# CircuitArd.net
KiCad netlist of a schematic drawn in EAGLE
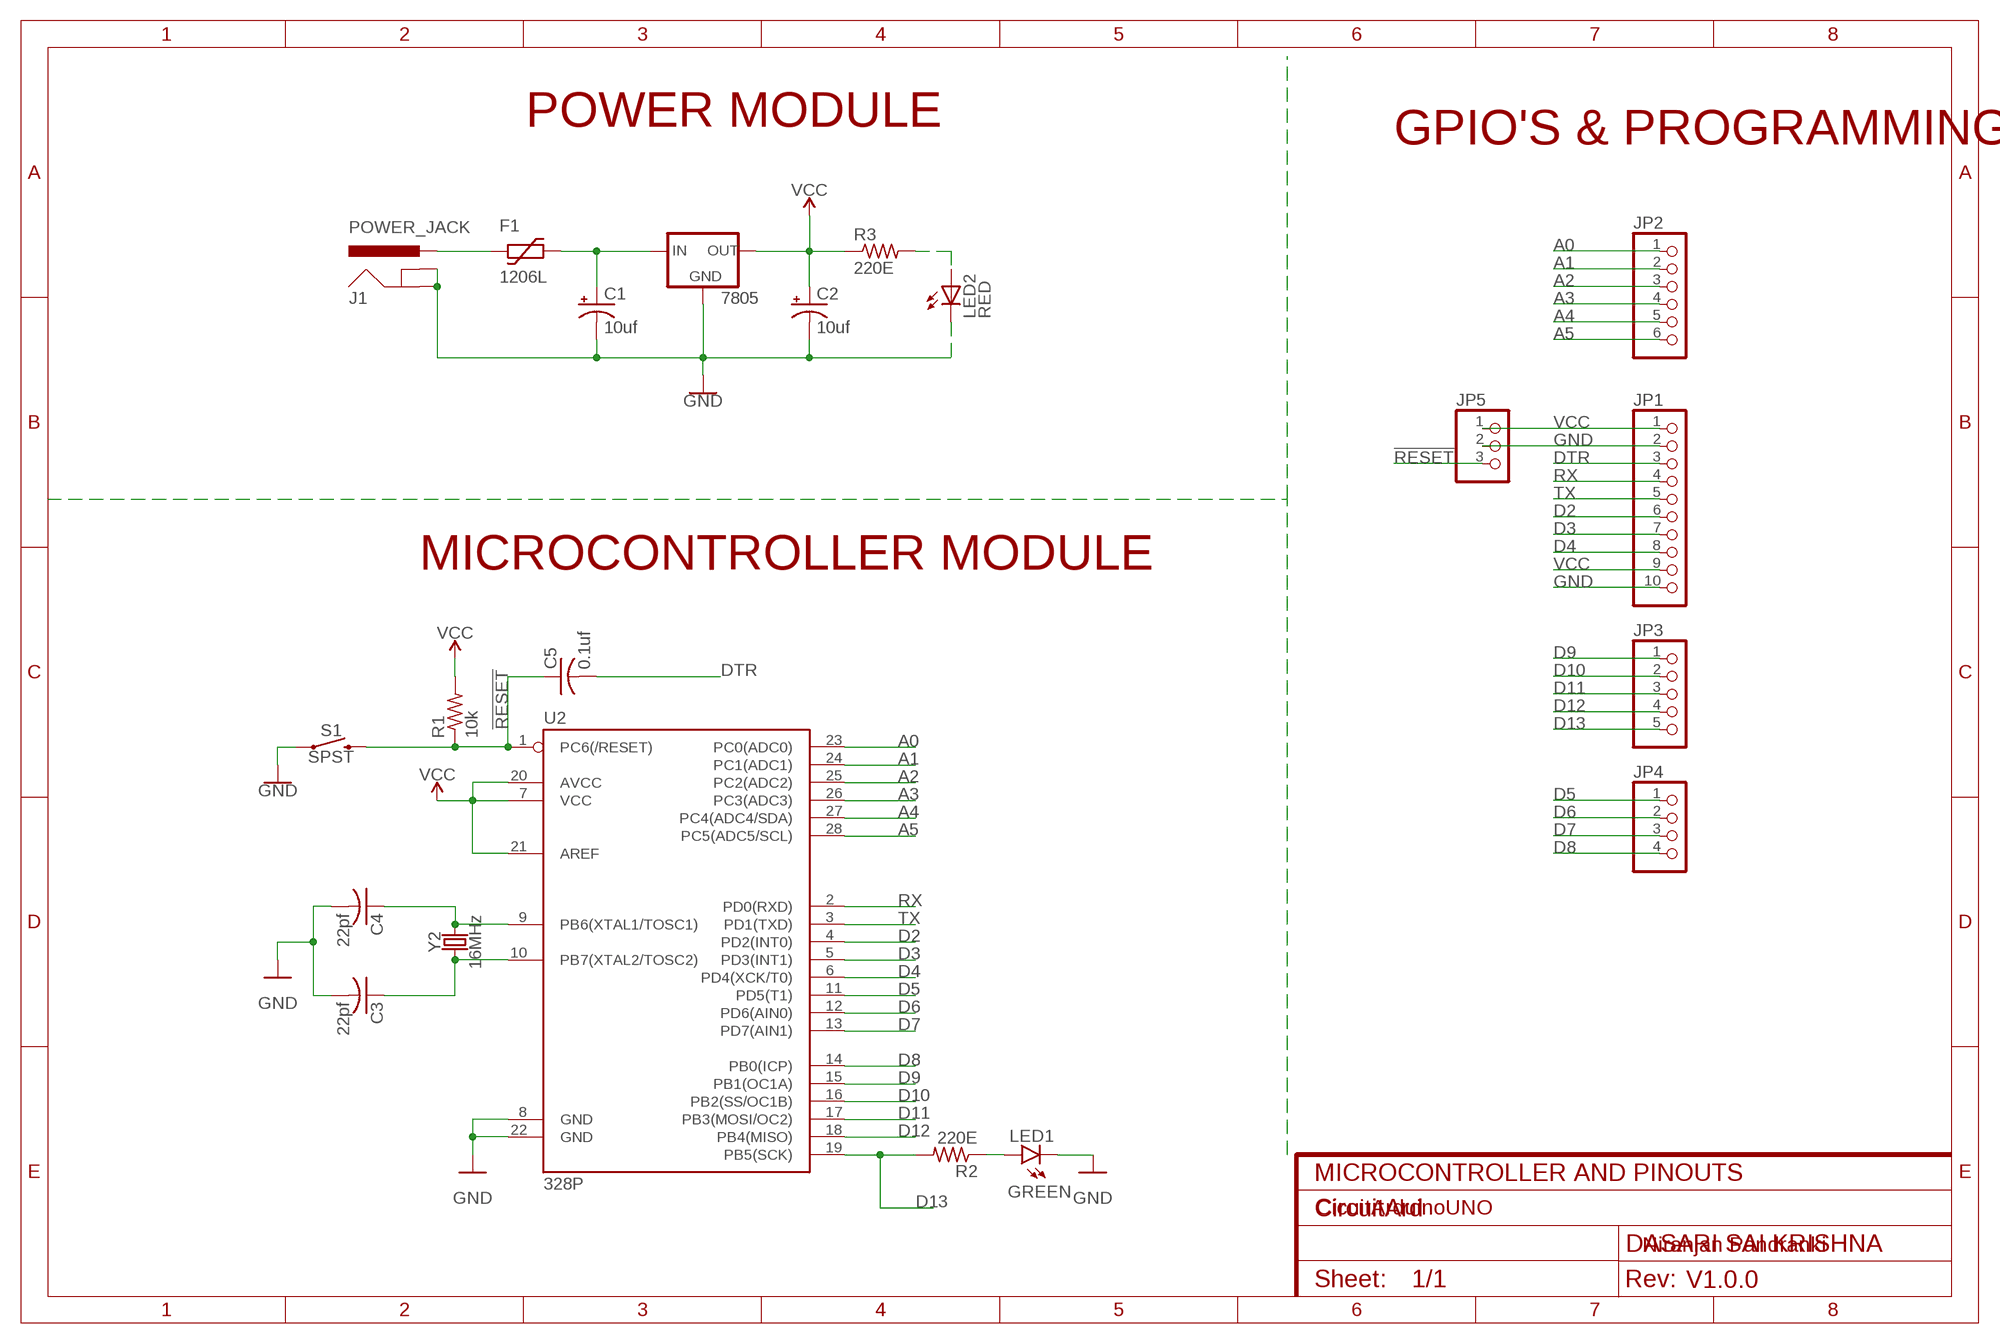
[diagram p0: schematic, sheet 1]

(export (version "E")
  (design (tool "Eeschema 10.0.6"))
  (components
    (comp (ref "C1")
      (value "10uf")
      (footprint "eagle-import:E2,5-6E")
      (libsource (lib "eagle-import") (part "CPOL-USE2,5-6E"))
    )
    (comp (ref "C2")
      (value "10uf")
      (footprint "eagle-import:E2,5-6E")
      (libsource (lib "eagle-import") (part "CPOL-USE2,5-6E"))
    )
    (comp (ref "C3")
      (value "22pf")
      (footprint "eagle-import:C025-024X044")
      (libsource (lib "eagle-import") (part "C-US025-024X044"))
    )
    (comp (ref "C4")
      (value "22pf")
      (footprint "eagle-import:C025-024X044")
      (libsource (lib "eagle-import") (part "C-US025-024X044"))
    )
    (comp (ref "C5")
      (value "0.1uf")
      (footprint "eagle-import:C025-024X044")
      (libsource (lib "eagle-import") (part "C-US025-024X044"))
    )
    (comp (ref "F1")
      (value "1206L")
      (footprint "eagle-import:1206L")
      (libsource (lib "eagle-import") (part "1206L"))
    )
    (comp (ref "IC1")
      (value "7805")
      (footprint "eagle-import:78XXS")
      (libsource (lib "eagle-import") (part "78XXS"))
    )
    (comp (ref "J1")
      (value "POWER_JACK")
      (footprint "eagle-import:POWER_JACK_PTH")
      (libsource (lib "eagle-import") (part "POWER_JACK"))
    )
    (comp (ref "JP1")
      (value "PINHD-1X10")
      (footprint "eagle-import:1X10")
      (libsource (lib "eagle-import") (part "PINHD-1X10"))
    )
    (comp (ref "JP2")
      (value "PINHD-1X6")
      (footprint "eagle-import:1X06")
      (libsource (lib "eagle-import") (part "PINHD-1X6"))
    )
    (comp (ref "JP3")
      (value "PINHD-1X5")
      (footprint "eagle-import:1X05")
      (libsource (lib "eagle-import") (part "PINHD-1X5"))
    )
    (comp (ref "JP4")
      (value "PINHD-1X4")
      (footprint "eagle-import:1X04")
      (libsource (lib "eagle-import") (part "PINHD-1X4"))
    )
    (comp (ref "JP5")
      (value "PINHD-1X3")
      (footprint "eagle-import:1X03")
      (libsource (lib "eagle-import") (part "PINHD-1X3"))
    )
    (comp (ref "LED1")
      (value "GREEN")
      (footprint "eagle-import:LED3MM")
      (libsource (lib "eagle-import") (part "led_259_LED3MM"))
    )
    (comp (ref "LED2")
      (value "RED")
      (footprint "eagle-import:LED3MM")
      (libsource (lib "eagle-import") (part "LED3MM"))
    )
    (comp (ref "R1")
      (value "10k")
      (footprint "eagle-import:0204_7")
      (libsource (lib "eagle-import") (part "R-US_0204/7"))
    )
    (comp (ref "R2")
      (value "220E")
      (footprint "eagle-import:0204_7")
      (libsource (lib "eagle-import") (part "R-US_0204/7"))
    )
    (comp (ref "R3")
      (value "220E")
      (footprint "eagle-import:0204_7")
      (libsource (lib "eagle-import") (part "R-US_0204/7"))
    )
    (comp (ref "S1")
      (value "SPST")
      (footprint "eagle-import:TACTILE_SWITCH_PTH_6.0MM")
      (libsource (lib "eagle-import") (part "MOMENTARY-SWITCH-SPST-PTH-6.0MM"))
    )
    (comp (ref "U2")
      (value "328P")
      (footprint "eagle-import:DIP28")
      (libsource (lib "eagle-import") (part "ATMEGA328P_PDIP"))
    )
    (comp (ref "Y2")
      (value "16MHz")
      (footprint "eagle-import:HC49US")
      (libsource (lib "eagle-import") (part "CRYSTAL-16MHZPTH-HC49US"))
    )
  )
  (nets
    (net (code "1") (name "/A0") (class "Default")
      (node (ref "JP2") (pin "1") (pinfunction "1_1") (pintype "passive"))
      (node (ref "U2") (pin "23") (pinfunction "PC0(ADC0)_23") (pintype "bidirectional"))
    )
    (net (code "2") (name "/A1") (class "Default")
      (node (ref "JP2") (pin "2") (pinfunction "2_2") (pintype "passive"))
      (node (ref "U2") (pin "24") (pinfunction "PC1(ADC1)_24") (pintype "bidirectional"))
    )
    (net (code "3") (name "/A2") (class "Default")
      (node (ref "JP2") (pin "3") (pinfunction "3_3") (pintype "passive"))
      (node (ref "U2") (pin "25") (pinfunction "PC2(ADC2)_25") (pintype "bidirectional"))
    )
    (net (code "4") (name "/A3") (class "Default")
      (node (ref "JP2") (pin "4") (pinfunction "4_4") (pintype "passive"))
      (node (ref "U2") (pin "26") (pinfunction "PC3(ADC3)_26") (pintype "bidirectional"))
    )
    (net (code "5") (name "/A4") (class "Default")
      (node (ref "JP2") (pin "5") (pinfunction "5_5") (pintype "passive"))
      (node (ref "U2") (pin "27") (pinfunction "PC4(ADC4/SDA)_27") (pintype "bidirectional"))
    )
    (net (code "6") (name "/A5") (class "Default")
      (node (ref "JP2") (pin "6") (pinfunction "6_6") (pintype "passive"))
      (node (ref "U2") (pin "28") (pinfunction "PC5(ADC5/SCL)_28") (pintype "bidirectional"))
    )
    (net (code "7") (name "/D2") (class "Default")
      (node (ref "JP1") (pin "6") (pinfunction "6_6") (pintype "passive"))
      (node (ref "U2") (pin "4") (pinfunction "PD2(INT0)_4") (pintype "bidirectional"))
    )
    (net (code "8") (name "/D3") (class "Default")
      (node (ref "JP1") (pin "7") (pinfunction "7_7") (pintype "passive"))
      (node (ref "U2") (pin "5") (pinfunction "PD3(INT1)_5") (pintype "bidirectional"))
    )
    (net (code "9") (name "/D4") (class "Default")
      (node (ref "JP1") (pin "8") (pinfunction "8_8") (pintype "passive"))
      (node (ref "U2") (pin "6") (pinfunction "PD4(XCK/T0)_6") (pintype "bidirectional"))
    )
    (net (code "10") (name "/D5") (class "Default")
      (node (ref "JP4") (pin "1") (pinfunction "1_1") (pintype "passive"))
      (node (ref "U2") (pin "11") (pinfunction "PD5(T1)_11") (pintype "bidirectional"))
    )
    (net (code "11") (name "/D6") (class "Default")
      (node (ref "JP4") (pin "2") (pinfunction "2_2") (pintype "passive"))
      (node (ref "U2") (pin "12") (pinfunction "PD6(AIN0)_12") (pintype "bidirectional"))
    )
    (net (code "12") (name "/D7") (class "Default")
      (node (ref "JP4") (pin "3") (pinfunction "3_3") (pintype "passive"))
      (node (ref "U2") (pin "13") (pinfunction "PD7(AIN1)_13") (pintype "bidirectional"))
    )
    (net (code "13") (name "/D8") (class "Default")
      (node (ref "JP4") (pin "4") (pinfunction "4_4") (pintype "passive"))
      (node (ref "U2") (pin "14") (pinfunction "PB0(ICP)_14") (pintype "bidirectional"))
    )
    (net (code "14") (name "/D9") (class "Default")
      (node (ref "JP3") (pin "1") (pinfunction "1_1") (pintype "passive"))
      (node (ref "U2") (pin "15") (pinfunction "PB1(OC1A)_15") (pintype "bidirectional"))
    )
    (net (code "15") (name "/D10") (class "Default")
      (node (ref "JP3") (pin "2") (pinfunction "2_2") (pintype "passive"))
      (node (ref "U2") (pin "16") (pinfunction "PB2(SS/OC1B)_16") (pintype "bidirectional"))
    )
    (net (code "16") (name "/D11") (class "Default")
      (node (ref "JP3") (pin "3") (pinfunction "3_3") (pintype "passive"))
      (node (ref "U2") (pin "17") (pinfunction "PB3(MOSI/OC2)_17") (pintype "bidirectional"))
    )
    (net (code "17") (name "/D12") (class "Default")
      (node (ref "JP3") (pin "4") (pinfunction "4_4") (pintype "passive"))
      (node (ref "U2") (pin "18") (pinfunction "PB4(MISO)_18") (pintype "bidirectional"))
    )
    (net (code "18") (name "/D13") (class "Default")
      (node (ref "JP3") (pin "5") (pinfunction "5_5") (pintype "passive"))
      (node (ref "R2") (pin "2") (pinfunction "2_2") (pintype "passive"))
      (node (ref "U2") (pin "19") (pinfunction "PB5(SCK)_19") (pintype "bidirectional"))
    )
    (net (code "19") (name "/DTR") (class "Default")
      (node (ref "C5") (pin "2") (pinfunction "2_2") (pintype "passive"))
      (node (ref "JP1") (pin "3") (pinfunction "3_3") (pintype "passive"))
    )
    (net (code "20") (name "/RX") (class "Default")
      (node (ref "JP1") (pin "4") (pinfunction "4_4") (pintype "passive"))
      (node (ref "U2") (pin "2") (pinfunction "PD0(RXD)_2") (pintype "bidirectional"))
    )
    (net (code "21") (name "/TX") (class "Default")
      (node (ref "JP1") (pin "5") (pinfunction "5_5") (pintype "passive"))
      (node (ref "U2") (pin "3") (pinfunction "PD1(TXD)_3") (pintype "bidirectional"))
    )
    (net (code "22") (name "/~{RESET}") (class "Default")
      (node (ref "C5") (pin "1") (pinfunction "1_1") (pintype "passive"))
      (node (ref "JP5") (pin "3") (pinfunction "3_3") (pintype "passive"))
      (node (ref "R1") (pin "1") (pinfunction "1_1") (pintype "passive"))
      (node (ref "S1") (pin "3") (pinfunction "2_3") (pintype "passive"))
      (node (ref "U2") (pin "1") (pinfunction "PC6(/RESET)_1") (pintype "bidirectional"))
    )
    (net (code "23") (name "GND") (class "Default")
      (node (ref "C1") (pin "-") (pinfunction "-_-") (pintype "passive"))
      (node (ref "C2") (pin "-") (pinfunction "-_-") (pintype "passive"))
      (node (ref "C3") (pin "2") (pinfunction "2_2") (pintype "passive"))
      (node (ref "C4") (pin "2") (pinfunction "2_2") (pintype "passive"))
      (node (ref "IC1") (pin "GND") (pinfunction "GND_GND") (pintype "input"))
      (node (ref "J1") (pin "GND") (pinfunction "GND_GND") (pintype "bidirectional"))
      (node (ref "J1") (pin "GNDBREAK") (pinfunction "GNDBREAK_GNDBREAK") (pintype "bidirectional"))
      (node (ref "JP1") (pin "10") (pinfunction "10_10") (pintype "passive"))
      (node (ref "JP1") (pin "2") (pinfunction "2_2") (pintype "passive"))
      (node (ref "JP5") (pin "2") (pinfunction "2_2") (pintype "passive"))
      (node (ref "LED1") (pin "K") (pinfunction "C_K") (pintype "passive"))
      (node (ref "LED2") (pin "K") (pinfunction "C_K") (pintype "passive"))
      (node (ref "S1") (pin "1") (pinfunction "1_1") (pintype "passive"))
      (node (ref "U2") (pin "22") (pinfunction "GND_22") (pintype "bidirectional"))
      (node (ref "U2") (pin "8") (pinfunction "GND_8") (pintype "bidirectional"))
    )
    (net (code "24") (name "Net-(F1-1)") (class "Default")
      (node (ref "F1") (pin "P$1") (pinfunction "1_P$1") (pintype "passive"))
      (node (ref "J1") (pin "PWR") (pinfunction "PWR_PWR") (pintype "bidirectional"))
    )
    (net (code "25") (name "Net-(F1-2)") (class "Default")
      (node (ref "C1") (pin "+") (pinfunction "+_+") (pintype "passive"))
      (node (ref "F1") (pin "P$2") (pinfunction "2_P$2") (pintype "passive"))
      (node (ref "IC1") (pin "IN") (pinfunction "IN_IN") (pintype "input"))
    )
    (net (code "26") (name "Net-(LED1-PadA)") (class "Default")
      (node (ref "LED1") (pin "A") (pinfunction "A_A") (pintype "passive"))
      (node (ref "R2") (pin "1") (pinfunction "1_1") (pintype "passive"))
    )
    (net (code "27") (name "Net-(LED2-PadA)") (class "Default")
      (node (ref "LED2") (pin "A") (pinfunction "A_A") (pintype "passive"))
      (node (ref "R3") (pin "2") (pinfunction "2_2") (pintype "passive"))
    )
    (net (code "28") (name "Net-(U2-PB6(XTAL1{slash}TOSC1))") (class "Default")
      (node (ref "C4") (pin "1") (pinfunction "1_1") (pintype "passive"))
      (node (ref "U2") (pin "9") (pinfunction "PB6(XTAL1/TOSC1)_9") (pintype "bidirectional"))
      (node (ref "Y2") (pin "2") (pinfunction "2_2") (pintype "passive"))
    )
    (net (code "29") (name "Net-(U2-PB7(XTAL2{slash}TOSC2))") (class "Default")
      (node (ref "C3") (pin "1") (pinfunction "1_1") (pintype "passive"))
      (node (ref "U2") (pin "10") (pinfunction "PB7(XTAL2/TOSC2)_10") (pintype "bidirectional"))
      (node (ref "Y2") (pin "1") (pinfunction "1_1") (pintype "passive"))
    )
    (net (code "30") (name "VCC") (class "Default")
      (node (ref "C2") (pin "+") (pinfunction "+_+") (pintype "passive"))
      (node (ref "IC1") (pin "OUT") (pinfunction "OUT_OUT") (pintype "passive"))
      (node (ref "JP1") (pin "1") (pinfunction "1_1") (pintype "passive"))
      (node (ref "JP1") (pin "9") (pinfunction "9_9") (pintype "passive"))
      (node (ref "JP5") (pin "1") (pinfunction "1_1") (pintype "passive"))
      (node (ref "R1") (pin "2") (pinfunction "2_2") (pintype "passive"))
      (node (ref "R3") (pin "1") (pinfunction "1_1") (pintype "passive"))
      (node (ref "U2") (pin "20") (pinfunction "AVCC_20") (pintype "bidirectional"))
      (node (ref "U2") (pin "21") (pinfunction "AREF_21") (pintype "bidirectional"))
      (node (ref "U2") (pin "7") (pinfunction "VCC_7") (pintype "bidirectional"))
    )
  )
)
